# CMoy-Pro-V_1_0_0_1.net
KiCad netlist of a schematic drawn in EAGLE
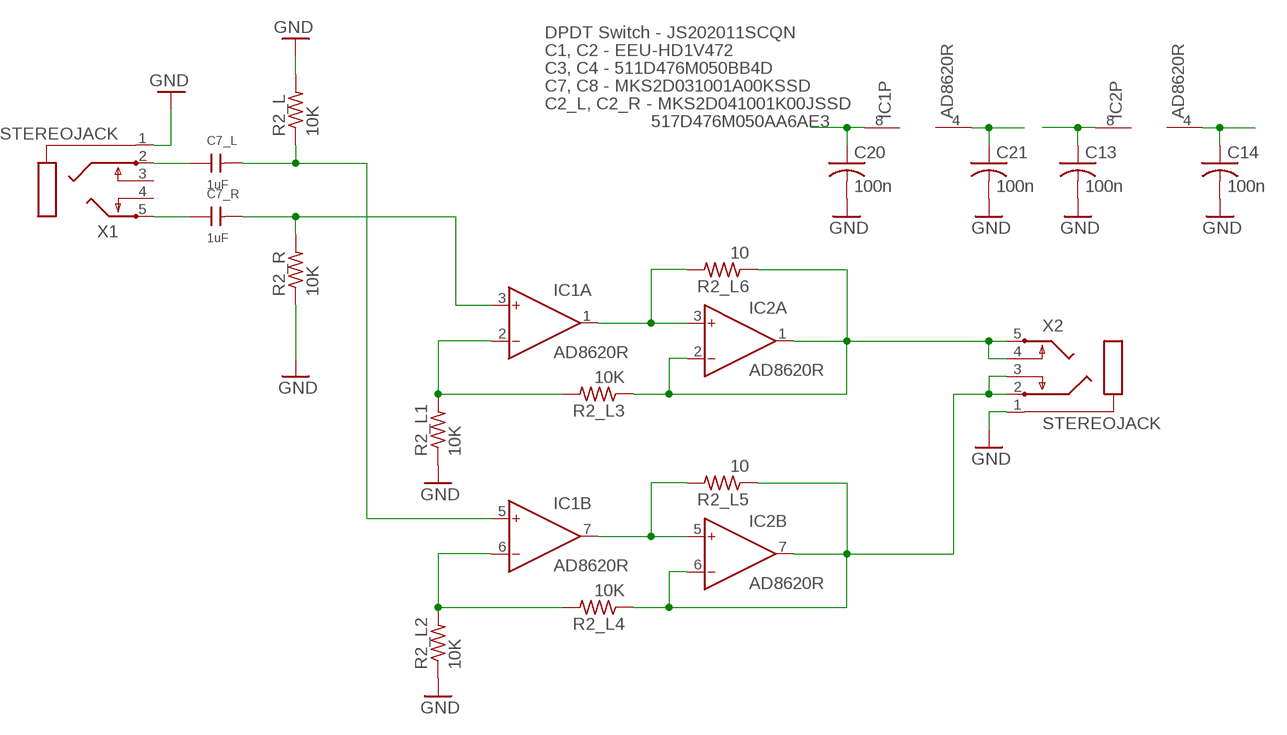
[diagram p0: schematic, sheet 1]
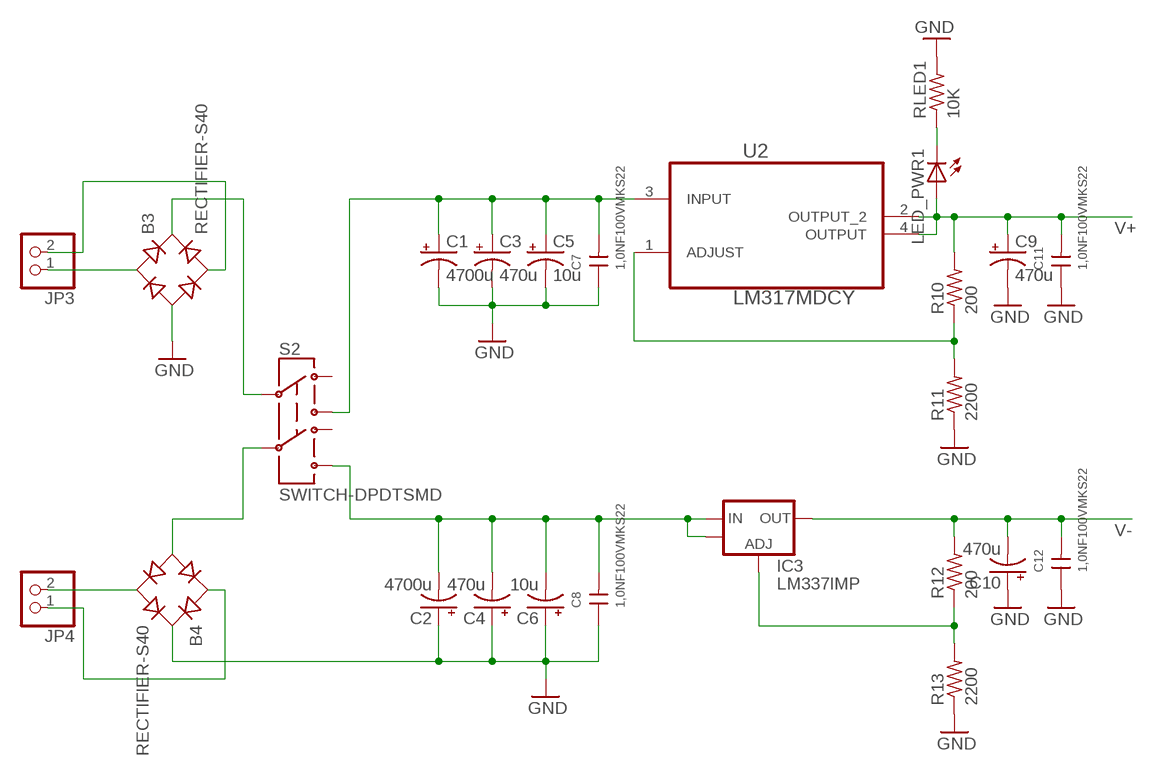
[diagram p1: schematic, sheet 2]

(export (version "E")
  (design (tool "Eeschema 10.0.6"))
  (components
    (comp (ref "C7_L")
      (value "1uF")
      (footprint "eagle-import:2,5X5,5RM5,0")
      (libsource (lib "eagle-import") (part "1,0NF100VMKS22"))
    )
    (comp (ref "C7_R")
      (value "1uF")
      (footprint "eagle-import:2,5X5,5RM5,0")
      (libsource (lib "eagle-import") (part "1,0NF100VMKS22"))
    )
    (comp (ref "C13")
      (value "100n")
      (footprint "eagle-import:C0603")
      (libsource (lib "eagle-import") (part "C-USC0603"))
    )
    (comp (ref "C14")
      (value "100n")
      (footprint "eagle-import:C0603")
      (libsource (lib "eagle-import") (part "C-USC0603"))
    )
    (comp (ref "C20")
      (value "100n")
      (footprint "eagle-import:C0603")
      (libsource (lib "eagle-import") (part "C-USC0603"))
    )
    (comp (ref "C21")
      (value "100n")
      (footprint "eagle-import:C0603")
      (libsource (lib "eagle-import") (part "C-USC0603"))
    )
    (comp (ref "IC1")
      (value "AD8620R")
      (footprint "eagle-import:SO8")
      (fields (field (name "MF") "ALTERA CORPORATION") (field (name "MPN") "AD8620ARZ"))
      (libsource (lib "eagle-import") (part "AD8620R"))
    )
    (comp (ref "IC2")
      (value "AD8620R")
      (footprint "eagle-import:SO8")
      (fields (field (name "MF") "ALTERA CORPORATION") (field (name "MPN") "AD8620ARZ"))
      (libsource (lib "eagle-import") (part "AD8620R"))
    )
    (comp (ref "R2_L")
      (value "10K")
      (footprint "eagle-import:0207_7")
      (libsource (lib "eagle-import") (part "R-US_0207/7"))
    )
    (comp (ref "R2_L1")
      (value "10K")
      (footprint "eagle-import:0207_7")
      (libsource (lib "eagle-import") (part "R-US_0207/7"))
    )
    (comp (ref "R2_L2")
      (value "10K")
      (footprint "eagle-import:0207_7")
      (libsource (lib "eagle-import") (part "R-US_0207/7"))
    )
    (comp (ref "R2_L3")
      (value "10K")
      (footprint "eagle-import:0207_7")
      (libsource (lib "eagle-import") (part "R-US_0207/7"))
    )
    (comp (ref "R2_L4")
      (value "10K")
      (footprint "eagle-import:0207_7")
      (libsource (lib "eagle-import") (part "R-US_0207/7"))
    )
    (comp (ref "R2_L5")
      (value "10")
      (footprint "eagle-import:0207_7")
      (libsource (lib "eagle-import") (part "R-US_0207/7"))
    )
    (comp (ref "R2_L6")
      (value "10")
      (footprint "eagle-import:0207_7")
      (libsource (lib "eagle-import") (part "R-US_0207/7"))
    )
    (comp (ref "R2_R")
      (value "10K")
      (footprint "eagle-import:0207_7")
      (libsource (lib "eagle-import") (part "R-US_0207/7"))
    )
    (comp (ref "X1")
      (value "STEREOJACK")
      (footprint "eagle-import:STX3100")
      (libsource (lib "eagle-import") (part "STEREOJACK"))
    )
    (comp (ref "X2")
      (value "STEREOJACK")
      (footprint "eagle-import:STX3100")
      (libsource (lib "eagle-import") (part "STEREOJACK"))
    )
    (comp (ref "B3")
      (value "RECTIFIER-S40")
      (footprint "eagle-import:TO-269AA")
      (libsource (lib "eagle-import") (part "RECTIFIER-S40"))
    )
    (comp (ref "B4")
      (value "RECTIFIER-S40")
      (footprint "eagle-import:TO-269AA")
      (libsource (lib "eagle-import") (part "RECTIFIER-S40"))
    )
    (comp (ref "C1")
      (value "4700u")
      (footprint "eagle-import:E7,5-16")
      (libsource (lib "eagle-import") (part "CPOL-USE7.5-16"))
    )
    (comp (ref "C2")
      (value "4700u")
      (footprint "eagle-import:E7,5-16")
      (libsource (lib "eagle-import") (part "CPOL-USE7.5-16"))
    )
    (comp (ref "C3")
      (value "470u")
      (footprint "eagle-import:E3,5-8")
      (libsource (lib "eagle-import") (part "CPOL-USE3.5-8"))
    )
    (comp (ref "C4")
      (value "470u")
      (footprint "eagle-import:E3,5-8")
      (libsource (lib "eagle-import") (part "CPOL-USE3.5-8"))
    )
    (comp (ref "C5")
      (value "10u")
      (footprint "eagle-import:E2-5")
      (libsource (lib "eagle-import") (part "CPOL-USE2-5"))
    )
    (comp (ref "C6")
      (value "10u")
      (footprint "eagle-import:E2-5")
      (libsource (lib "eagle-import") (part "CPOL-USE2-5"))
    )
    (comp (ref "C7")
      (value "1,0NF100VMKS22")
      (footprint "eagle-import:2,5X5,5RM5,0")
      (libsource (lib "eagle-import") (part "1,0NF100VMKS22"))
    )
    (comp (ref "C8")
      (value "1,0NF100VMKS22")
      (footprint "eagle-import:2,5X5,5RM5,0")
      (libsource (lib "eagle-import") (part "1,0NF100VMKS22"))
    )
    (comp (ref "C9")
      (value "470u")
      (footprint "eagle-import:E3,5-8")
      (libsource (lib "eagle-import") (part "CPOL-USE3.5-8"))
    )
    (comp (ref "C10")
      (value "470u")
      (footprint "eagle-import:E3,5-8")
      (libsource (lib "eagle-import") (part "CPOL-USE3.5-8"))
    )
    (comp (ref "C11")
      (value "1,0NF100VMKS22")
      (footprint "eagle-import:2,5X5,5RM5,0")
      (libsource (lib "eagle-import") (part "1,0NF100VMKS22"))
    )
    (comp (ref "C12")
      (value "1,0NF100VMKS22")
      (footprint "eagle-import:2,5X5,5RM5,0")
      (libsource (lib "eagle-import") (part "1,0NF100VMKS22"))
    )
    (comp (ref "IC3")
      (value "LM337IMP")
      (footprint "eagle-import:SOT-223")
      (libsource (lib "eagle-import") (part "LM337IMP"))
    )
    (comp (ref "JP3")
      (value "PINHD-1X2")
      (footprint "eagle-import:1X02")
      (libsource (lib "eagle-import") (part "PINHD-1X2"))
    )
    (comp (ref "JP4")
      (value "PINHD-1X2")
      (footprint "eagle-import:1X02")
      (libsource (lib "eagle-import") (part "PINHD-1X2"))
    )
    (comp (ref "LED_PWR1")
      (value "LEDCHIP-LED0603")
      (footprint "eagle-import:CHIP-LED0603")
      (libsource (lib "eagle-import") (part "LEDCHIP-LED0603"))
    )
    (comp (ref "R10")
      (value "200")
      (footprint "eagle-import:R0603")
      (libsource (lib "eagle-import") (part "R-US_R0603"))
    )
    (comp (ref "R11")
      (value "2200")
      (footprint "eagle-import:R0603")
      (libsource (lib "eagle-import") (part "R-US_R0603"))
    )
    (comp (ref "R12")
      (value "200")
      (footprint "eagle-import:R0603")
      (libsource (lib "eagle-import") (part "R-US_R0603"))
    )
    (comp (ref "R13")
      (value "2200")
      (footprint "eagle-import:R0603")
      (libsource (lib "eagle-import") (part "R-US_R0603"))
    )
    (comp (ref "RLED1")
      (value "10K")
      (footprint "eagle-import:R0603")
      (libsource (lib "eagle-import") (part "R-US_R0603"))
    )
    (comp (ref "S2")
      (value "SWITCH-DPDTSMD")
      (footprint "eagle-import:AYZ0202")
      (libsource (lib "eagle-import") (part "SWITCH-DPDTSMD"))
    )
    (comp (ref "U2")
      (value "LM317MDCY")
      (footprint "eagle-import:SOT230P700X180-4N")
      (libsource (lib "eagle-import") (part "LM317MDCY"))
    )
  )
  (nets
    (net (code "1") (name "GND") (class "Default")
      (node (ref "B3") (pin "-") (pinfunction "-_-") (pintype "passive"))
      (node (ref "B4") (pin "+") (pinfunction "+_+") (pintype "passive"))
      (node (ref "C1") (pin "-") (pinfunction "-_-") (pintype "passive"))
      (node (ref "C10") (pin "+") (pinfunction "+_+") (pintype "passive"))
      (node (ref "C11") (pin "1") (pinfunction "1_1") (pintype "passive"))
      (node (ref "C12") (pin "1") (pinfunction "1_1") (pintype "passive"))
      (node (ref "C13") (pin "2") (pinfunction "2_2") (pintype "passive"))
      (node (ref "C14") (pin "2") (pinfunction "2_2") (pintype "passive"))
      (node (ref "C2") (pin "+") (pinfunction "+_+") (pintype "passive"))
      (node (ref "C20") (pin "2") (pinfunction "2_2") (pintype "passive"))
      (node (ref "C21") (pin "2") (pinfunction "2_2") (pintype "passive"))
      (node (ref "C3") (pin "-") (pinfunction "-_-") (pintype "passive"))
      (node (ref "C4") (pin "+") (pinfunction "+_+") (pintype "passive"))
      (node (ref "C5") (pin "-") (pinfunction "-_-") (pintype "passive"))
      (node (ref "C6") (pin "+") (pinfunction "+_+") (pintype "passive"))
      (node (ref "C7") (pin "1") (pinfunction "1_1") (pintype "passive"))
      (node (ref "C8") (pin "1") (pinfunction "1_1") (pintype "passive"))
      (node (ref "C9") (pin "-") (pinfunction "-_-") (pintype "passive"))
      (node (ref "R11") (pin "1") (pinfunction "1_1") (pintype "passive"))
      (node (ref "R13") (pin "1") (pinfunction "1_1") (pintype "passive"))
      (node (ref "R2_L") (pin "2") (pinfunction "2_2") (pintype "passive"))
      (node (ref "R2_L1") (pin "1") (pinfunction "1_1") (pintype "passive"))
      (node (ref "R2_L2") (pin "1") (pinfunction "1_1") (pintype "passive"))
      (node (ref "R2_R") (pin "1") (pinfunction "1_1") (pintype "passive"))
      (node (ref "RLED1") (pin "2") (pinfunction "2_2") (pintype "passive"))
      (node (ref "X1") (pin "1") (pinfunction "1_1") (pintype "passive"))
      (node (ref "X2") (pin "1") (pinfunction "1_1") (pintype "passive"))
    )
    (net (code "2") (name "Net-(B3-Pad+)") (class "Default")
      (node (ref "B3") (pin "+") (pinfunction "+_+") (pintype "passive"))
      (node (ref "S2") (pin "2") (pinfunction "2_2") (pintype "bidirectional"))
    )
    (net (code "3") (name "Net-(B3-PadAC1)") (class "Default")
      (node (ref "B3") (pin "AC1") (pinfunction "AC1_AC1") (pintype "passive"))
      (node (ref "JP3") (pin "1") (pinfunction "1_1") (pintype "passive"))
    )
    (net (code "4") (name "Net-(B3-PadAC2)") (class "Default")
      (node (ref "B3") (pin "AC2") (pinfunction "AC2_AC2") (pintype "passive"))
      (node (ref "JP3") (pin "2") (pinfunction "2_2") (pintype "passive"))
    )
    (net (code "5") (name "Net-(B4-Pad-)") (class "Default")
      (node (ref "B4") (pin "-") (pinfunction "-_-") (pintype "passive"))
      (node (ref "S2") (pin "5") (pinfunction "5_5") (pintype "bidirectional"))
    )
    (net (code "6") (name "Net-(B4-PadAC1)") (class "Default")
      (node (ref "B4") (pin "AC1") (pinfunction "AC1_AC1") (pintype "passive"))
      (node (ref "JP4") (pin "1") (pinfunction "1_1") (pintype "passive"))
    )
    (net (code "7") (name "Net-(B4-PadAC2)") (class "Default")
      (node (ref "B4") (pin "AC2") (pinfunction "AC2_AC2") (pintype "passive"))
      (node (ref "JP4") (pin "2") (pinfunction "2_2") (pintype "passive"))
    )
    (net (code "8") (name "Net-(C7_L-Pad1)") (class "Default")
      (node (ref "C7_L") (pin "1") (pinfunction "1_1") (pintype "passive"))
      (node (ref "X1") (pin "2") (pinfunction "2_2") (pintype "passive"))
    )
    (net (code "9") (name "Net-(C7_R-Pad1)") (class "Default")
      (node (ref "C7_R") (pin "1") (pinfunction "1_1") (pintype "passive"))
      (node (ref "X1") (pin "5") (pinfunction "5_5") (pintype "passive"))
    )
    (net (code "10") (name "Net-(IC1A-IN+)") (class "Default")
      (node (ref "C7_R") (pin "2") (pinfunction "2_2") (pintype "passive"))
      (node (ref "IC1") (pin "3") (pinfunction "IN+_3") (pintype "input"))
      (node (ref "R2_R") (pin "2") (pinfunction "2_2") (pintype "passive"))
    )
    (net (code "11") (name "Net-(IC1A-IN-)") (class "Default")
      (node (ref "IC1") (pin "2") (pinfunction "IN-_2") (pintype "input"))
      (node (ref "R2_L1") (pin "2") (pinfunction "2_2") (pintype "passive"))
      (node (ref "R2_L3") (pin "2") (pinfunction "2_2") (pintype "passive"))
    )
    (net (code "12") (name "Net-(IC1A-OUT)") (class "Default")
      (node (ref "IC1") (pin "1") (pinfunction "OUT_1") (pintype "output"))
      (node (ref "IC2") (pin "3") (pinfunction "IN+_3") (pintype "input"))
      (node (ref "R2_L6") (pin "2") (pinfunction "2_2") (pintype "passive"))
    )
    (net (code "13") (name "Net-(IC1B-IN+)") (class "Default")
      (node (ref "C7_L") (pin "2") (pinfunction "2_2") (pintype "passive"))
      (node (ref "IC1") (pin "5") (pinfunction "IN+_5") (pintype "input"))
      (node (ref "R2_L") (pin "1") (pinfunction "1_1") (pintype "passive"))
    )
    (net (code "14") (name "Net-(IC1B-IN-)") (class "Default")
      (node (ref "IC1") (pin "6") (pinfunction "IN-_6") (pintype "input"))
      (node (ref "R2_L2") (pin "2") (pinfunction "2_2") (pintype "passive"))
      (node (ref "R2_L4") (pin "2") (pinfunction "2_2") (pintype "passive"))
    )
    (net (code "15") (name "Net-(IC1B-OUT)") (class "Default")
      (node (ref "IC1") (pin "7") (pinfunction "OUT_7") (pintype "output"))
      (node (ref "IC2") (pin "5") (pinfunction "IN+_5") (pintype "input"))
      (node (ref "R2_L5") (pin "2") (pinfunction "2_2") (pintype "passive"))
    )
    (net (code "16") (name "Net-(IC2A-IN-)") (class "Default")
      (node (ref "IC2") (pin "1") (pinfunction "OUT_1") (pintype "output"))
      (node (ref "IC2") (pin "2") (pinfunction "IN-_2") (pintype "input"))
      (node (ref "R2_L3") (pin "1") (pinfunction "1_1") (pintype "passive"))
      (node (ref "R2_L6") (pin "1") (pinfunction "1_1") (pintype "passive"))
      (node (ref "X2") (pin "4") (pinfunction "4_4") (pintype "passive"))
      (node (ref "X2") (pin "5") (pinfunction "5_5") (pintype "passive"))
    )
    (net (code "17") (name "Net-(IC2B-IN-)") (class "Default")
      (node (ref "IC2") (pin "6") (pinfunction "IN-_6") (pintype "input"))
      (node (ref "IC2") (pin "7") (pinfunction "OUT_7") (pintype "output"))
      (node (ref "R2_L4") (pin "1") (pinfunction "1_1") (pintype "passive"))
      (node (ref "R2_L5") (pin "1") (pinfunction "1_1") (pintype "passive"))
      (node (ref "X2") (pin "2") (pinfunction "2_2") (pintype "passive"))
      (node (ref "X2") (pin "3") (pinfunction "3_3") (pintype "passive"))
    )
    (net (code "18") (name "Net-(IC3-ADJ)") (class "Default")
      (node (ref "IC3") (pin "1") (pinfunction "ADJ_1") (pintype "input"))
      (node (ref "R12") (pin "1") (pinfunction "1_1") (pintype "passive"))
      (node (ref "R13") (pin "2") (pinfunction "2_2") (pintype "passive"))
    )
    (net (code "19") (name "Net-(IC3-IN)") (class "Default")
      (node (ref "C2") (pin "-") (pinfunction "-_-") (pintype "passive"))
      (node (ref "C4") (pin "-") (pinfunction "-_-") (pintype "passive"))
      (node (ref "C6") (pin "-") (pinfunction "-_-") (pintype "passive"))
      (node (ref "C8") (pin "2") (pinfunction "2_2") (pintype "passive"))
      (node (ref "IC3") (pin "2") (pinfunction "IN_2") (pintype "input"))
      (node (ref "IC3") (pin "4") (pinfunction "P$1_4") (pintype "bidirectional"))
      (node (ref "S2") (pin "6") (pinfunction "6_6") (pintype "bidirectional"))
    )
    (net (code "20") (name "Net-(LED_PWR1-PadC)") (class "Default")
      (node (ref "LED_PWR1") (pin "C") (pinfunction "C_C") (pintype "passive"))
      (node (ref "RLED1") (pin "1") (pinfunction "1_1") (pintype "passive"))
    )
    (net (code "21") (name "Net-(U2-ADJUST)") (class "Default")
      (node (ref "R10") (pin "1") (pinfunction "1_1") (pintype "passive"))
      (node (ref "R11") (pin "2") (pinfunction "2_2") (pintype "passive"))
      (node (ref "U2") (pin "1") (pinfunction "ADJUST_1") (pintype "input"))
    )
    (net (code "22") (name "Net-(U2-INPUT)") (class "Default")
      (node (ref "C1") (pin "+") (pinfunction "+_+") (pintype "passive"))
      (node (ref "C3") (pin "+") (pinfunction "+_+") (pintype "passive"))
      (node (ref "C5") (pin "+") (pinfunction "+_+") (pintype "passive"))
      (node (ref "C7") (pin "2") (pinfunction "2_2") (pintype "passive"))
      (node (ref "S2") (pin "3") (pinfunction "3_3") (pintype "bidirectional"))
      (node (ref "U2") (pin "3") (pinfunction "INPUT_3") (pintype "input"))
    )
    (net (code "23") (name "V+") (class "Default")
      (node (ref "C11") (pin "2") (pinfunction "2_2") (pintype "passive"))
      (node (ref "C13") (pin "1") (pinfunction "1_1") (pintype "passive"))
      (node (ref "C20") (pin "1") (pinfunction "1_1") (pintype "passive"))
      (node (ref "C9") (pin "+") (pinfunction "+_+") (pintype "passive"))
      (node (ref "IC1") (pin "8") (pinfunction "V+_8") (pintype "power_in"))
      (node (ref "IC2") (pin "8") (pinfunction "V+_8") (pintype "power_in"))
      (node (ref "LED_PWR1") (pin "A") (pinfunction "A_A") (pintype "passive"))
      (node (ref "R10") (pin "2") (pinfunction "2_2") (pintype "passive"))
      (node (ref "U2") (pin "2") (pinfunction "OUTPUT_2_2") (pintype "output"))
      (node (ref "U2") (pin "4") (pinfunction "OUTPUT_4") (pintype "output"))
    )
    (net (code "24") (name "V-") (class "Default")
      (node (ref "C10") (pin "-") (pinfunction "-_-") (pintype "passive"))
      (node (ref "C12") (pin "2") (pinfunction "2_2") (pintype "passive"))
      (node (ref "C14") (pin "1") (pinfunction "1_1") (pintype "passive"))
      (node (ref "C21") (pin "1") (pinfunction "1_1") (pintype "passive"))
      (node (ref "IC1") (pin "4") (pinfunction "V-_4") (pintype "power_in"))
      (node (ref "IC2") (pin "4") (pinfunction "V-_4") (pintype "power_in"))
      (node (ref "IC3") (pin "3") (pinfunction "OUT_3") (pintype "passive"))
      (node (ref "R12") (pin "2") (pinfunction "2_2") (pintype "passive"))
    )
    (net (code "25") (name "unconnected-(S2-Pad1)") (class "Default")
      (node (ref "S2") (pin "1") (pinfunction "1_1") (pintype "bidirectional"))
    )
    (net (code "26") (name "unconnected-(S2-Pad4)") (class "Default")
      (node (ref "S2") (pin "4") (pinfunction "4_4") (pintype "bidirectional"))
    )
    (net (code "27") (name "unconnected-(X1-Pad3)") (class "Default")
      (node (ref "X1") (pin "3") (pinfunction "3_3") (pintype "passive"))
    )
    (net (code "28") (name "unconnected-(X1-Pad4)") (class "Default")
      (node (ref "X1") (pin "4") (pinfunction "4_4") (pintype "passive"))
    )
  )
)
